# garw_joystick.net
KiCad netlist of a schematic drawn in EAGLE
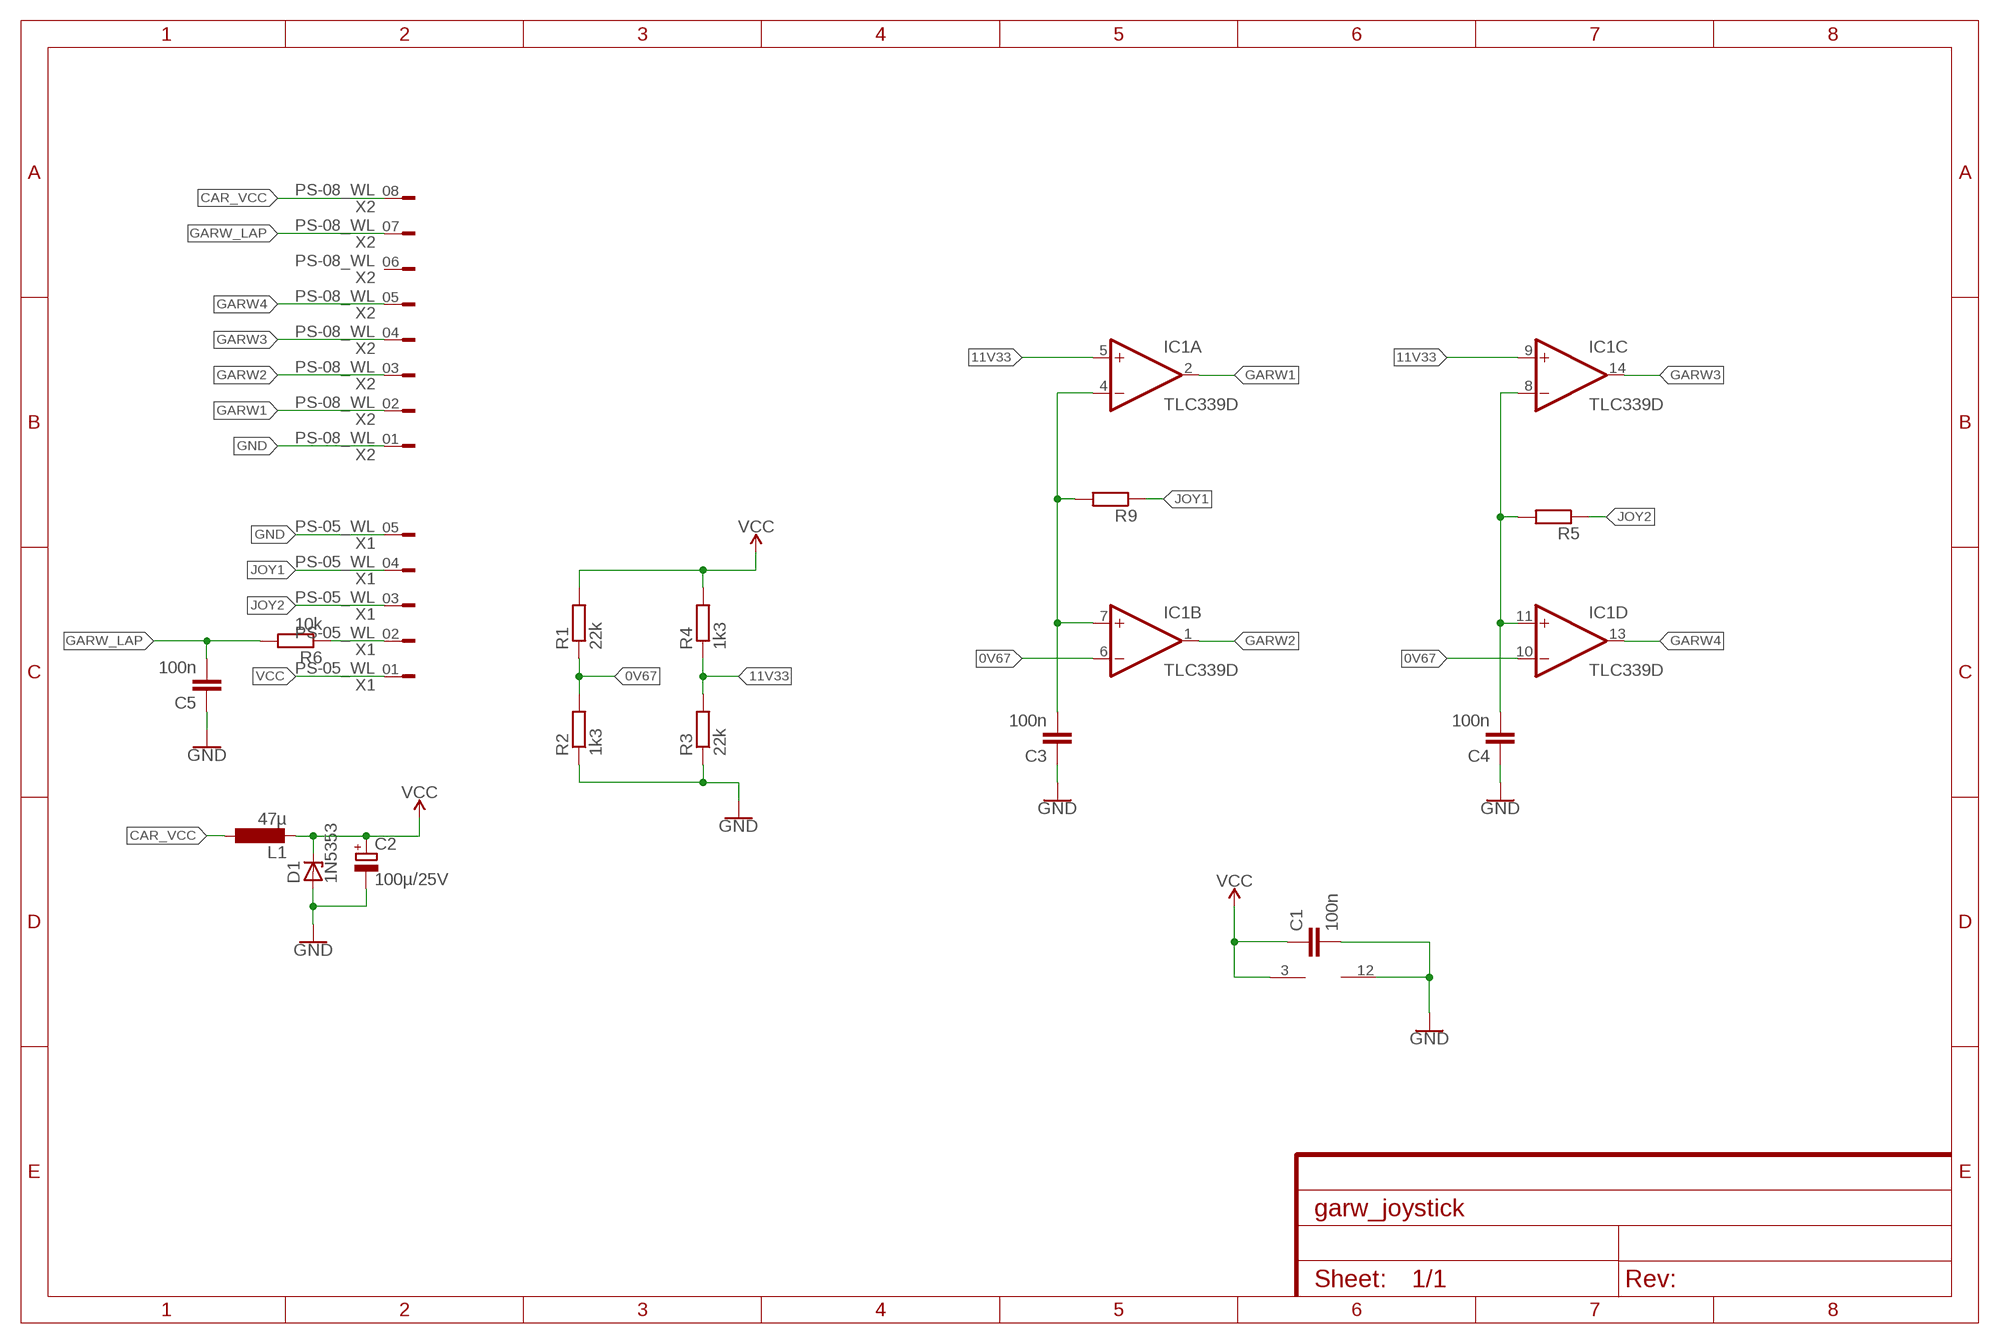
[diagram p0: schematic, sheet 1]

(export (version "E")
  (design (tool "Eeschema 10.0.6"))
  (components
    (comp (ref "C1")
      (value "100n")
      (footprint "eagle-import:C0805")
      (libsource (lib "eagle-import") (part "C-EUC0805"))
    )
    (comp (ref "C2")
      (value "100µ/25V")
      (footprint "eagle-import:153CLV-0605")
      (libsource (lib "eagle-import") (part "CPOL-EU153CLV-0605"))
    )
    (comp (ref "C3")
      (value "100n")
      (footprint "eagle-import:C0805")
      (libsource (lib "eagle-import") (part "C-EUC0805"))
    )
    (comp (ref "C4")
      (value "100n")
      (footprint "eagle-import:C0805")
      (libsource (lib "eagle-import") (part "C-EUC0805"))
    )
    (comp (ref "C5")
      (value "100n")
      (footprint "eagle-import:C0805")
      (libsource (lib "eagle-import") (part "C-EUC0805"))
    )
    (comp (ref "D1")
      (value "1N5353")
      (footprint "eagle-import:DO35Z10")
      (libsource (lib "eagle-import") (part "ZENER-DIODEDO35Z10"))
    )
    (comp (ref "IC1")
      (value "TLC339D")
      (footprint "eagle-import:SO14")
      (libsource (lib "eagle-import") (part "TLC339D"))
    )
    (comp (ref "L1")
      (value "47µ")
      (footprint "eagle-import:0204_7")
      (libsource (lib "eagle-import") (part "L-EU0204/7"))
    )
    (comp (ref "R1")
      (value "22k")
      (footprint "eagle-import:M0805")
      (libsource (lib "eagle-import") (part "R-EU_M0805"))
    )
    (comp (ref "R2")
      (value "1k3")
      (footprint "eagle-import:M0805")
      (libsource (lib "eagle-import") (part "R-EU_M0805"))
    )
    (comp (ref "R3")
      (value "22k")
      (footprint "eagle-import:M0805")
      (libsource (lib "eagle-import") (part "R-EU_M0805"))
    )
    (comp (ref "R4")
      (value "1k3")
      (footprint "eagle-import:M0805")
      (libsource (lib "eagle-import") (part "R-EU_M0805"))
    )
    (comp (ref "R5")
      (value "R-EU_M0805")
      (footprint "eagle-import:M0805")
      (libsource (lib "eagle-import") (part "R-EU_M0805"))
    )
    (comp (ref "R6")
      (value "10k")
      (footprint "eagle-import:M0805")
      (libsource (lib "eagle-import") (part "R-EU_M0805"))
    )
    (comp (ref "R9")
      (value "R-EU_M0805")
      (footprint "eagle-import:M0805")
      (libsource (lib "eagle-import") (part "R-EU_M0805"))
    )
    (comp (ref "X1")
      (value "PS-05_WL")
      (footprint "eagle-import:PS-05_WL")
      (libsource (lib "eagle-import") (part "PS-05_WL"))
    )
    (comp (ref "X2")
      (value "PS-08_WL")
      (footprint "eagle-import:PS-08_WL")
      (libsource (lib "eagle-import") (part "PS-08_WL"))
    )
  )
  (nets
    (net (code "1") (name "0V67") (class "Default")
      (node (ref "IC1") (pin "10") (pinfunction "-IN_10") (pintype "input"))
      (node (ref "IC1") (pin "6") (pinfunction "-IN_6") (pintype "input"))
      (node (ref "R1") (pin "1") (pinfunction "1_1") (pintype "passive"))
      (node (ref "R2") (pin "2") (pinfunction "2_2") (pintype "passive"))
    )
    (net (code "2") (name "11V33") (class "Default")
      (node (ref "IC1") (pin "5") (pinfunction "+IN_5") (pintype "input"))
      (node (ref "IC1") (pin "9") (pinfunction "+IN_9") (pintype "input"))
      (node (ref "R3") (pin "2") (pinfunction "2_2") (pintype "passive"))
      (node (ref "R4") (pin "1") (pinfunction "1_1") (pintype "passive"))
    )
    (net (code "3") (name "CAR_VCC") (class "Default")
      (node (ref "L1") (pin "1") (pinfunction "1_1") (pintype "passive"))
      (node (ref "X2") (pin "08") (pinfunction "P$1_08") (pintype "passive"))
    )
    (net (code "4") (name "GARW1") (class "Default")
      (node (ref "IC1") (pin "2") (pinfunction "OUT_2") (pintype "output"))
      (node (ref "X2") (pin "02") (pinfunction "P$1_02") (pintype "passive"))
    )
    (net (code "5") (name "GARW2") (class "Default")
      (node (ref "IC1") (pin "1") (pinfunction "OUT_1") (pintype "output"))
      (node (ref "X2") (pin "03") (pinfunction "P$1_03") (pintype "passive"))
    )
    (net (code "6") (name "GARW3") (class "Default")
      (node (ref "IC1") (pin "14") (pinfunction "OUT_14") (pintype "output"))
      (node (ref "X2") (pin "04") (pinfunction "P$1_04") (pintype "passive"))
    )
    (net (code "7") (name "GARW4") (class "Default")
      (node (ref "IC1") (pin "13") (pinfunction "OUT_13") (pintype "output"))
      (node (ref "X2") (pin "05") (pinfunction "P$1_05") (pintype "passive"))
    )
    (net (code "8") (name "GARW_LAP") (class "Default")
      (node (ref "C5") (pin "2") (pinfunction "2_2") (pintype "passive"))
      (node (ref "R6") (pin "2") (pinfunction "2_2") (pintype "passive"))
      (node (ref "X2") (pin "07") (pinfunction "P$1_07") (pintype "passive"))
    )
    (net (code "9") (name "GND") (class "Default")
      (node (ref "C1") (pin "2") (pinfunction "2_2") (pintype "passive"))
      (node (ref "C2") (pin "-") (pinfunction "-_-") (pintype "passive"))
      (node (ref "C3") (pin "1") (pinfunction "1_1") (pintype "passive"))
      (node (ref "C4") (pin "1") (pinfunction "1_1") (pintype "passive"))
      (node (ref "C5") (pin "1") (pinfunction "1_1") (pintype "passive"))
      (node (ref "D1") (pin "A") (pinfunction "A_A") (pintype "passive"))
      (node (ref "IC1") (pin "12") (pinfunction "V-_12") (pintype "power_in"))
      (node (ref "R2") (pin "1") (pinfunction "1_1") (pintype "passive"))
      (node (ref "R3") (pin "1") (pinfunction "1_1") (pintype "passive"))
      (node (ref "X1") (pin "05") (pinfunction "P$1_05") (pintype "passive"))
      (node (ref "X2") (pin "01") (pinfunction "P$1_01") (pintype "passive"))
    )
    (net (code "10") (name "JOY1") (class "Default")
      (node (ref "R9") (pin "1") (pinfunction "1_1") (pintype "passive"))
      (node (ref "X1") (pin "04") (pinfunction "P$1_04") (pintype "passive"))
    )
    (net (code "11") (name "JOY2") (class "Default")
      (node (ref "R5") (pin "1") (pinfunction "1_1") (pintype "passive"))
      (node (ref "X1") (pin "03") (pinfunction "P$1_03") (pintype "passive"))
    )
    (net (code "12") (name "Net-(IC1A--IN)") (class "Default")
      (node (ref "C3") (pin "2") (pinfunction "2_2") (pintype "passive"))
      (node (ref "IC1") (pin "4") (pinfunction "-IN_4") (pintype "input"))
      (node (ref "IC1") (pin "7") (pinfunction "+IN_7") (pintype "input"))
      (node (ref "R9") (pin "2") (pinfunction "2_2") (pintype "passive"))
    )
    (net (code "13") (name "Net-(IC1C--IN)") (class "Default")
      (node (ref "C4") (pin "2") (pinfunction "2_2") (pintype "passive"))
      (node (ref "IC1") (pin "11") (pinfunction "+IN_11") (pintype "input"))
      (node (ref "IC1") (pin "8") (pinfunction "-IN_8") (pintype "input"))
      (node (ref "R5") (pin "2") (pinfunction "2_2") (pintype "passive"))
    )
    (net (code "14") (name "Net-(X1B-P$1)") (class "Default")
      (node (ref "R6") (pin "1") (pinfunction "1_1") (pintype "passive"))
      (node (ref "X1") (pin "02") (pinfunction "P$1_02") (pintype "passive"))
    )
    (net (code "15") (name "VCC") (class "Default")
      (node (ref "C1") (pin "1") (pinfunction "1_1") (pintype "passive"))
      (node (ref "C2") (pin "+") (pinfunction "+_+") (pintype "passive"))
      (node (ref "D1") (pin "C") (pinfunction "C_C") (pintype "passive"))
      (node (ref "IC1") (pin "3") (pinfunction "V+_3") (pintype "power_in"))
      (node (ref "L1") (pin "2") (pinfunction "2_2") (pintype "passive"))
      (node (ref "R1") (pin "2") (pinfunction "2_2") (pintype "passive"))
      (node (ref "R4") (pin "2") (pinfunction "2_2") (pintype "passive"))
      (node (ref "X1") (pin "01") (pinfunction "P$1_01") (pintype "passive"))
    )
    (net (code "16") (name "unconnected-(X2F-P$1-Pad06)") (class "Default")
      (node (ref "X2") (pin "06") (pinfunction "P$1_06") (pintype "passive"))
    )
  )
)
